# holo_clock_1.net
KiCad netlist of a schematic drawn in EAGLE
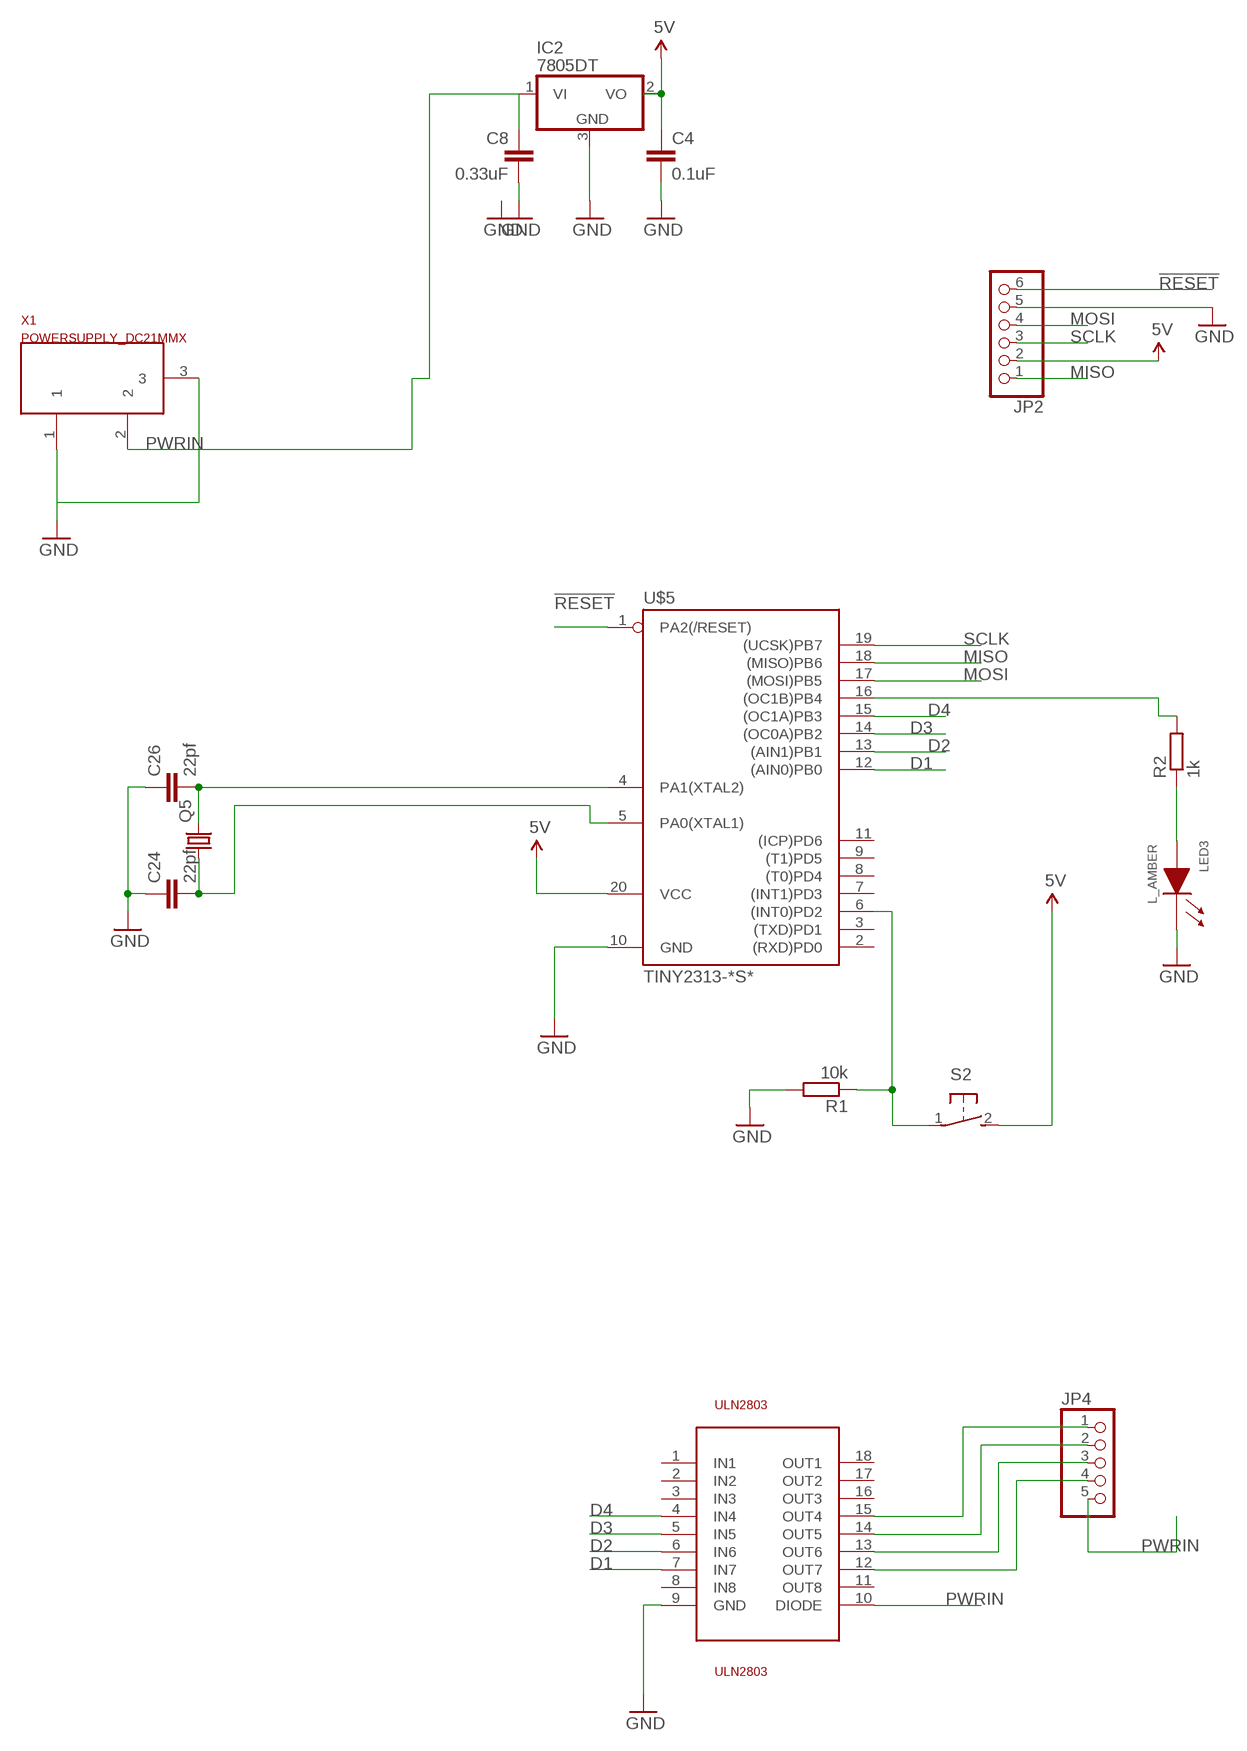
[diagram p0: schematic, sheet 1]

(export (version "E")
  (design (tool "Eeschema 10.0.6"))
  (components
    (comp (ref "C4")
      (value "0.1uF")
      (footprint "eagle-import:CAP-PTH-SMALL2")
      (libsource (lib "eagle-import") (part "CAPPTH2"))
    )
    (comp (ref "C8")
      (value "0.33uF")
      (footprint "eagle-import:CAP-PTH-SMALL2")
      (libsource (lib "eagle-import") (part "CAPPTH2"))
    )
    (comp (ref "C24")
      (value "22pf")
      (footprint "eagle-import:0805")
      (libsource (lib "eagle-import") (part "CAP0805"))
    )
    (comp (ref "C26")
      (value "22pf")
      (footprint "eagle-import:0805")
      (libsource (lib "eagle-import") (part "CAP0805"))
    )
    (comp (ref "IC2")
      (value "7805DT")
      (footprint "eagle-import:TO252")
      (libsource (lib "eagle-import") (part "78DT05"))
    )
    (comp (ref "JP2")
      (value "PINHD-1X6")
      (footprint "eagle-import:1X06")
      (libsource (lib "eagle-import") (part "PINHD-1X6"))
    )
    (comp (ref "JP4")
      (value "PINHD-1X5")
      (footprint "eagle-import:1X05")
      (libsource (lib "eagle-import") (part "PINHD-1X5"))
    )
    (comp (ref "LED3")
      (value "L_AMBER")
      (footprint "eagle-import:LED0805")
      (libsource (lib "eagle-import") (part "LED0805"))
    )
    (comp (ref "Q5")
      (value "CRYSTALHC49S")
      (footprint "eagle-import:HC49_S")
      (libsource (lib "eagle-import") (part "CRYSTALHC49S"))
    )
    (comp (ref "R1")
      (value "10k")
      (footprint "eagle-import:R0805")
      (libsource (lib "eagle-import") (part "R-EU_R0805"))
    )
    (comp (ref "R2")
      (value "1k")
      (footprint "eagle-import:R0805")
      (libsource (lib "eagle-import") (part "R-EU_R0805"))
    )
    (comp (ref "S2")
      (value "31-XX")
      (footprint "eagle-import:B3F-31XX")
      (fields (field (name "MPN") "B3F-3100"))
      (libsource (lib "eagle-import") (part "31-XX"))
    )
    (comp (ref "U$5")
      (value "TINY2313-*S*")
      (footprint "eagle-import:SO20L$")
      (libsource (lib "eagle-import") (part "TINY2313-S"))
    )
    (comp (ref "ULN2803")
      (value "ULN2803")
      (footprint "eagle-import:SO18L")
      (libsource (lib "eagle-import") (part "ULN2803"))
    )
    (comp (ref "X1")
      (value "POWERSUPPLY_DC21MMX")
      (footprint "eagle-import:POWERSUPPLY_DC-21MM")
      (libsource (lib "eagle-import") (part "POWERSUPPLY_DC21MMX"))
    )
  )
  (nets
    (net (code "1") (name "/D1") (class "Default")
      (node (ref "U$5") (pin "12") (pinfunction "(AIN0)PB0_12") (pintype "bidirectional"))
      (node (ref "ULN2803") (pin "7") (pinfunction "IN7_7") (pintype "input"))
    )
    (net (code "2") (name "/D2") (class "Default")
      (node (ref "U$5") (pin "13") (pinfunction "(AIN1)PB1_13") (pintype "bidirectional"))
      (node (ref "ULN2803") (pin "6") (pinfunction "IN6_6") (pintype "input"))
    )
    (net (code "3") (name "/D3") (class "Default")
      (node (ref "U$5") (pin "14") (pinfunction "(OC0A)PB2_14") (pintype "bidirectional"))
      (node (ref "ULN2803") (pin "5") (pinfunction "IN5_5") (pintype "input"))
    )
    (net (code "4") (name "/D4") (class "Default")
      (node (ref "U$5") (pin "15") (pinfunction "(OC1A)PB3_15") (pintype "bidirectional"))
      (node (ref "ULN2803") (pin "4") (pinfunction "IN4_4") (pintype "input"))
    )
    (net (code "5") (name "/MISO") (class "Default")
      (node (ref "JP2") (pin "1") (pinfunction "1_1") (pintype "passive"))
      (node (ref "U$5") (pin "18") (pinfunction "(MISO)PB6_18") (pintype "bidirectional"))
    )
    (net (code "6") (name "/MOSI") (class "Default")
      (node (ref "JP2") (pin "4") (pinfunction "4_4") (pintype "passive"))
      (node (ref "U$5") (pin "17") (pinfunction "(MOSI)PB5_17") (pintype "bidirectional"))
    )
    (net (code "7") (name "/PWRIN") (class "Default")
      (node (ref "C8") (pin "1") (pinfunction "1_1") (pintype "passive"))
      (node (ref "IC2") (pin "1") (pinfunction "VI_1") (pintype "input"))
      (node (ref "JP4") (pin "5") (pinfunction "5_5") (pintype "passive"))
      (node (ref "ULN2803") (pin "10") (pinfunction "DIODE_10") (pintype "power_in"))
      (node (ref "X1") (pin "2") (pinfunction "2_2") (pintype "power_in"))
    )
    (net (code "8") (name "/SCLK") (class "Default")
      (node (ref "JP2") (pin "3") (pinfunction "3_3") (pintype "passive"))
      (node (ref "U$5") (pin "19") (pinfunction "(UCSK)PB7_19") (pintype "bidirectional"))
    )
    (net (code "9") (name "/~{RESET}") (class "Default")
      (node (ref "JP2") (pin "6") (pinfunction "6_6") (pintype "passive"))
      (node (ref "U$5") (pin "1") (pinfunction "PA2(/RESET)_1") (pintype "input"))
    )
    (net (code "10") (name "5V") (class "Default")
      (node (ref "C4") (pin "1") (pinfunction "1_1") (pintype "passive"))
      (node (ref "IC2") (pin "2") (pinfunction "VO_2") (pintype "passive"))
      (node (ref "JP2") (pin "2") (pinfunction "2_2") (pintype "passive"))
      (node (ref "S2") (pin "2") (pinfunction "S_2") (pintype "passive"))
      (node (ref "U$5") (pin "20") (pinfunction "VCC_20") (pintype "power_in"))
    )
    (net (code "11") (name "GND") (class "Default")
      (node (ref "C24") (pin "1") (pinfunction "1_1") (pintype "passive"))
      (node (ref "C26") (pin "1") (pinfunction "1_1") (pintype "passive"))
      (node (ref "C4") (pin "2") (pinfunction "2_2") (pintype "passive"))
      (node (ref "C8") (pin "2") (pinfunction "2_2") (pintype "passive"))
      (node (ref "IC2") (pin "3") (pinfunction "GND_3") (pintype "passive"))
      (node (ref "JP2") (pin "5") (pinfunction "5_5") (pintype "passive"))
      (node (ref "LED3") (pin "1") (pinfunction "CA_1") (pintype "passive"))
      (node (ref "R1") (pin "2") (pinfunction "2_2") (pintype "passive"))
      (node (ref "U$5") (pin "10") (pinfunction "GND_10") (pintype "power_in"))
      (node (ref "ULN2803") (pin "9") (pinfunction "GND_9") (pintype "power_in"))
      (node (ref "X1") (pin "1") (pinfunction "1_1") (pintype "power_in"))
      (node (ref "X1") (pin "3") (pinfunction "3_3") (pintype "power_in"))
    )
    (net (code "12") (name "Net-(LED3-AN)") (class "Default")
      (node (ref "LED3") (pin "2") (pinfunction "AN_2") (pintype "passive"))
      (node (ref "R2") (pin "1") (pinfunction "1_1") (pintype "passive"))
    )
    (net (code "13") (name "Net-(S2-P)") (class "Default")
      (node (ref "R1") (pin "1") (pinfunction "1_1") (pintype "passive"))
      (node (ref "S2") (pin "1") (pinfunction "P_1") (pintype "passive"))
      (node (ref "U$5") (pin "6") (pinfunction "(INT0)PD2_6") (pintype "bidirectional"))
    )
    (net (code "14") (name "Net-(U$5-(OC1B)PB4)") (class "Default")
      (node (ref "R2") (pin "2") (pinfunction "2_2") (pintype "passive"))
      (node (ref "U$5") (pin "16") (pinfunction "(OC1B)PB4_16") (pintype "bidirectional"))
    )
    (net (code "15") (name "Net-(U$5-PA0(XTAL1))") (class "Default")
      (node (ref "C24") (pin "2") (pinfunction "2_2") (pintype "passive"))
      (node (ref "Q5") (pin "1") (pinfunction "1_1") (pintype "passive"))
      (node (ref "U$5") (pin "5") (pinfunction "PA0(XTAL1)_5") (pintype "bidirectional"))
    )
    (net (code "16") (name "Net-(U$5-PA1(XTAL2))") (class "Default")
      (node (ref "C26") (pin "2") (pinfunction "2_2") (pintype "passive"))
      (node (ref "Q5") (pin "2") (pinfunction "2_2") (pintype "passive"))
      (node (ref "U$5") (pin "4") (pinfunction "PA1(XTAL2)_4") (pintype "bidirectional"))
    )
    (net (code "17") (name "Net-(ULN2803-OUT4)") (class "Default")
      (node (ref "JP4") (pin "1") (pinfunction "1_1") (pintype "passive"))
      (node (ref "ULN2803") (pin "15") (pinfunction "OUT4_15") (pintype "open_collector"))
    )
    (net (code "18") (name "Net-(ULN2803-OUT5)") (class "Default")
      (node (ref "JP4") (pin "2") (pinfunction "2_2") (pintype "passive"))
      (node (ref "ULN2803") (pin "14") (pinfunction "OUT5_14") (pintype "open_collector"))
    )
    (net (code "19") (name "Net-(ULN2803-OUT6)") (class "Default")
      (node (ref "JP4") (pin "3") (pinfunction "3_3") (pintype "passive"))
      (node (ref "ULN2803") (pin "13") (pinfunction "OUT6_13") (pintype "open_collector"))
    )
    (net (code "20") (name "Net-(ULN2803-OUT7)") (class "Default")
      (node (ref "JP4") (pin "4") (pinfunction "4_4") (pintype "passive"))
      (node (ref "ULN2803") (pin "12") (pinfunction "OUT7_12") (pintype "open_collector"))
    )
    (net (code "21") (name "unconnected-(U$5-(ICP)PD6-Pad11)") (class "Default")
      (node (ref "U$5") (pin "11") (pinfunction "(ICP)PD6_11") (pintype "bidirectional"))
    )
    (net (code "22") (name "unconnected-(U$5-(INT1)PD3-Pad7)") (class "Default")
      (node (ref "U$5") (pin "7") (pinfunction "(INT1)PD3_7") (pintype "bidirectional"))
    )
    (net (code "23") (name "unconnected-(U$5-(RXD)PD0-Pad2)") (class "Default")
      (node (ref "U$5") (pin "2") (pinfunction "(RXD)PD0_2") (pintype "bidirectional"))
    )
    (net (code "24") (name "unconnected-(U$5-(T0)PD4-Pad8)") (class "Default")
      (node (ref "U$5") (pin "8") (pinfunction "(T0)PD4_8") (pintype "bidirectional"))
    )
    (net (code "25") (name "unconnected-(U$5-(T1)PD5-Pad9)") (class "Default")
      (node (ref "U$5") (pin "9") (pinfunction "(T1)PD5_9") (pintype "bidirectional"))
    )
    (net (code "26") (name "unconnected-(U$5-(TXD)PD1-Pad3)") (class "Default")
      (node (ref "U$5") (pin "3") (pinfunction "(TXD)PD1_3") (pintype "bidirectional"))
    )
    (net (code "27") (name "unconnected-(ULN2803-IN1-Pad1)") (class "Default")
      (node (ref "ULN2803") (pin "1") (pinfunction "IN1_1") (pintype "input"))
    )
    (net (code "28") (name "unconnected-(ULN2803-IN2-Pad2)") (class "Default")
      (node (ref "ULN2803") (pin "2") (pinfunction "IN2_2") (pintype "input"))
    )
    (net (code "29") (name "unconnected-(ULN2803-IN3-Pad3)") (class "Default")
      (node (ref "ULN2803") (pin "3") (pinfunction "IN3_3") (pintype "input"))
    )
    (net (code "30") (name "unconnected-(ULN2803-IN8-Pad8)") (class "Default")
      (node (ref "ULN2803") (pin "8") (pinfunction "IN8_8") (pintype "input"))
    )
    (net (code "31") (name "unconnected-(ULN2803-OUT1-Pad18)") (class "Default")
      (node (ref "ULN2803") (pin "18") (pinfunction "OUT1_18") (pintype "open_collector"))
    )
    (net (code "32") (name "unconnected-(ULN2803-OUT2-Pad17)") (class "Default")
      (node (ref "ULN2803") (pin "17") (pinfunction "OUT2_17") (pintype "open_collector"))
    )
    (net (code "33") (name "unconnected-(ULN2803-OUT3-Pad16)") (class "Default")
      (node (ref "ULN2803") (pin "16") (pinfunction "OUT3_16") (pintype "open_collector"))
    )
    (net (code "34") (name "unconnected-(ULN2803-OUT8-Pad11)") (class "Default")
      (node (ref "ULN2803") (pin "11") (pinfunction "OUT8_11") (pintype "open_collector"))
    )
  )
)
